# DRV8462.net
KiCad netlist of a schematic drawn in Altium Designer
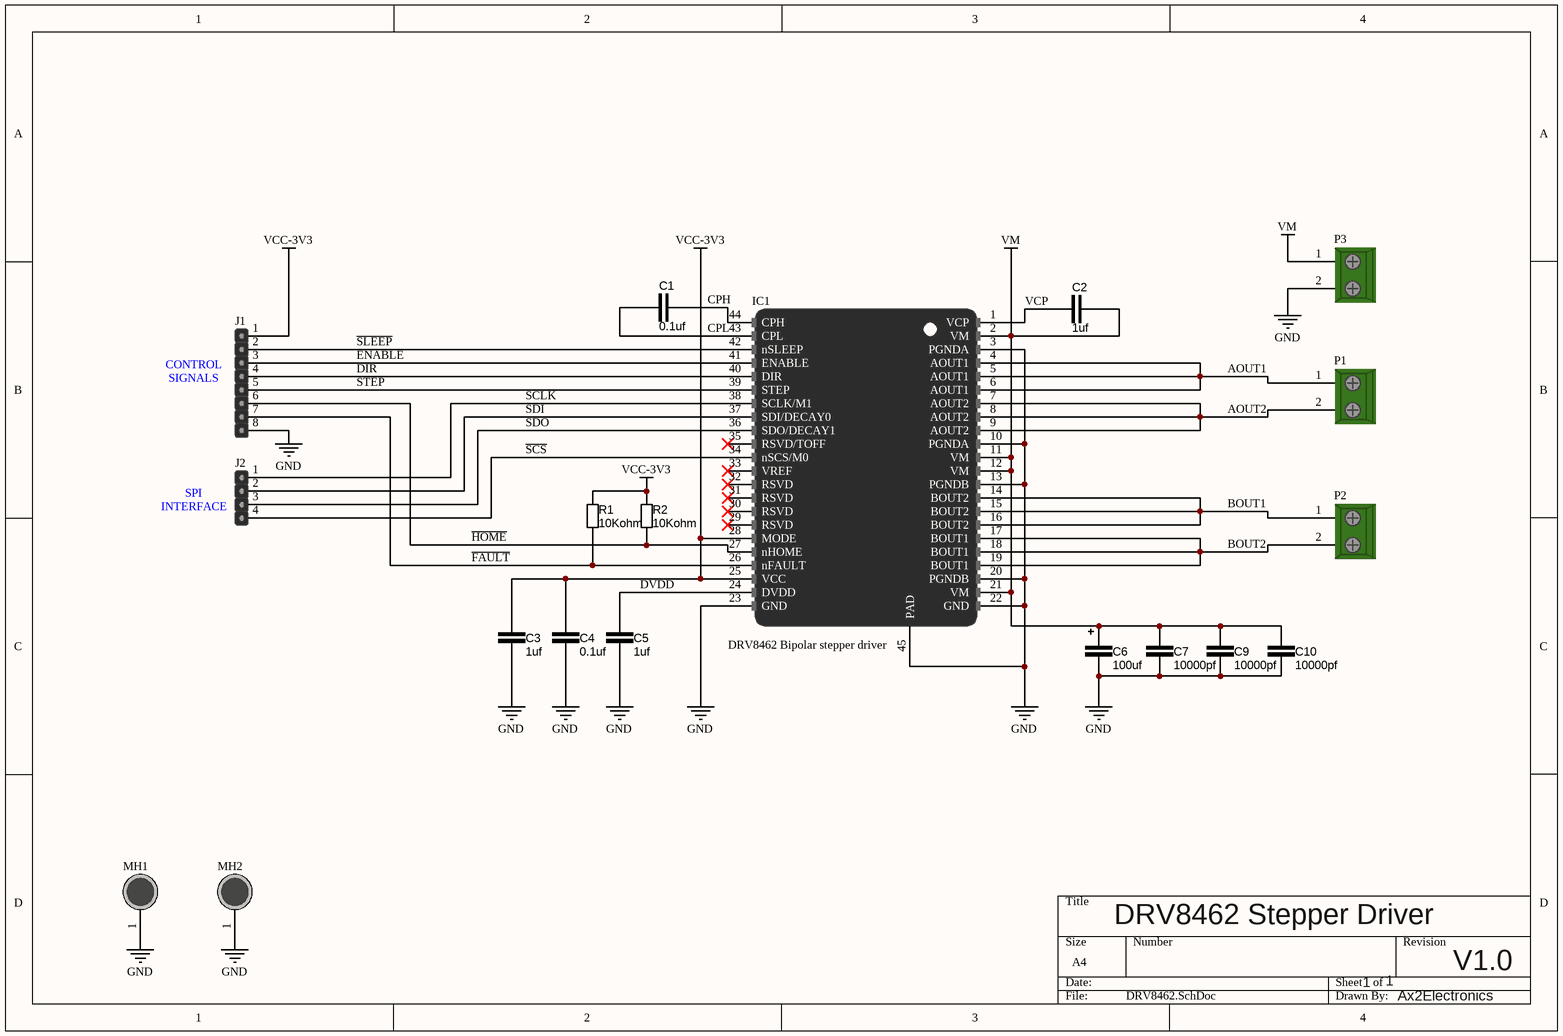
[diagram p0: DRV8462.SchDoc]

(export (version "E")
  (design (tool "Eeschema 10.0.6"))
  (components
    (comp (ref "C1")
      (value "0.1uf")
      (footprint "CAP_0603")
      (description "CAP CER 0.1uF 10V X7R 0603")
      (fields (field (name "DIGIKEY PART NUMBER") "732-7939-2-ND"))
      (libsource (lib "") (part "0000012_1"))
    )
    (comp (ref "C2")
      (value "1uf")
      (footprint "CAP_0603")
      (description "CAP CER 1uF 0603 16V X7R")
      (fields (field (name "DIGIKEY PART NUMBER") "1276-1019-2-ND"))
      (libsource (lib "CapacitorsIntegrated") (part "0000009"))
    )
    (comp (ref "C3")
      (value "1uf")
      (footprint "CAP_0603")
      (description "CAP CER 1uF 10V X7R 0603")
      (fields (field (name "DIGIKEY PART NUMBER") "1276-1946-2-ND"))
      (libsource (lib "CapacitorsIntegrated") (part "0000011"))
    )
    (comp (ref "C4")
      (value "0.1uf")
      (footprint "CAP_0603")
      (description "CAP CER 0.1uF 10V X7R 0603")
      (fields (field (name "DIGIKEY PART NUMBER") "732-7939-2-ND"))
      (libsource (lib "CapacitorsIntegrated") (part "0000012"))
    )
    (comp (ref "C5")
      (value "1uf")
      (footprint "CAP_0603")
      (description "CAP CER 1uF 0603 16V X7R")
      (fields (field (name "DIGIKEY PART NUMBER") "1276-1019-2-ND"))
      (libsource (lib "") (part "0000009_1"))
    )
    (comp (ref "C6")
      (value "100uf")
      (footprint "CAPAE7366X60M")
      (description "CAP ALUM POLY 100UF 20% 63V SMD")
      (fields (field (name "DIGIKEY PART NUMBER") "399-15648-2-ND"))
      (libsource (lib "CapacitorsIntegrated") (part "0000013"))
    )
    (comp (ref "C7")
      (value "10000pf")
      (footprint "CAP_0603")
      (description "CAP CER 10000PF 63V X7R 0603")
      (fields (field (name "DIGIKEY PART NUMBER") "1608-1294-2-ND"))
      (libsource (lib "CapacitorsIntegrated") (part "0000010"))
    )
    (comp (ref "C9")
      (value "10000pf")
      (footprint "CAP_0603")
      (description "CAP CER 10000PF 63V X7R 0603")
      (fields (field (name "DIGIKEY PART NUMBER") "1608-1294-2-ND"))
      (libsource (lib "CapacitorsIntegrated") (part "0000010"))
    )
    (comp (ref "C10")
      (value "10000pf")
      (footprint "CAP_0603")
      (description "CAP CER 10000PF 63V X7R 0603")
      (fields (field (name "DIGIKEY PART NUMBER") "1608-1294-2-ND"))
      (libsource (lib "CapacitorsIntegrated") (part "0000010"))
    )
    (comp (ref "IC1")
      (value "DRV8462 Bipolar stepper driver")
      (footprint "TSOP64P810X120_HS-45N")
      (description "65-V, 10-A, DUAL H-BRIDGE STEPPER DRIVER")
      (fields
        (field (name "DIGIKEY PART NUMBER") "296-DRV8462DDWRTR-ND")
        (field (name "MOUSER PART NUMBER") "595-DRV8462DDWR")
      )
      (libsource (lib "IntegratedCircuits") (part "DRV8462"))
    )
    (comp (ref "J1")
      (value "Header 8 PIN")
      (footprint "HEADER_8PIN")
      (libsource (lib "ElectroMechanical") (part "00000005"))
    )
    (comp (ref "J2")
      (value "Header 4 PIN")
      (footprint "HEADER_4PIN")
      (libsource (lib "ElectroMechanical") (part "00000004"))
    )
    (comp (ref "MH1")
      (value "Mounting Hole")
      (footprint "HOLE-3mm")
      (description "Mounting Hole 3mm")
      (libsource (lib "ElectroMechanical") (part "00000006"))
    )
    (comp (ref "MH2")
      (value "Mounting Hole")
      (footprint "HOLE-3mm")
      (description "Mounting Hole 3mm")
      (libsource (lib "ElectroMechanical") (part "00000006"))
    )
    (comp (ref "P1")
      (value "Terminal Block")
      (footprint "TERM_BLOCK 5mm 2PIN")
      (description "Terminal block 90 deg 5mm 2PIN")
      (fields (field (name "DIGIKEY PART NUMBER") "2057-EB20-02-C-ND"))
      (libsource (lib "ElectroMechanical") (part "00000001"))
    )
    (comp (ref "P2")
      (value "Terminal Block")
      (footprint "TERM_BLOCK 5mm 2PIN")
      (description "Terminal block 90 deg 5mm 2PIN")
      (fields (field (name "DIGIKEY PART NUMBER") "2057-EB20-02-C-ND"))
      (libsource (lib "ElectroMechanical") (part "00000001"))
    )
    (comp (ref "P3")
      (value "Terminal Block")
      (footprint "TERM_BLOCK 5mm 2PIN")
      (description "Terminal block 90 deg 5mm 2PIN")
      (fields (field (name "DIGIKEY PART NUMBER") "2057-EB20-02-C-ND"))
      (libsource (lib "ElectroMechanical") (part "00000001"))
    )
    (comp (ref "R1")
      (value "10Kohm")
      (footprint "RES_0603")
      (description "RES 10K OHM 1% 1/10W 0603")
      (libsource (lib "ResistorsIntegrated") (part "R000001"))
    )
    (comp (ref "R2")
      (value "10Kohm")
      (footprint "RES_0603")
      (description "RES 10K OHM 1% 1/10W 0603")
      (libsource (lib "ResistorsIntegrated") (part "R000001"))
    )
  )
  (nets
    (net (code "1") (name "/AOUT1") (class "Default")
      (node (ref "IC1") (pin "4") (pinfunction "AOUT1_4") (pintype "passive"))
      (node (ref "IC1") (pin "5") (pinfunction "AOUT1_5") (pintype "passive"))
      (node (ref "IC1") (pin "6") (pinfunction "AOUT1_6") (pintype "passive"))
      (node (ref "P1") (pin "1") (pinfunction "pin1_1") (pintype "passive"))
    )
    (net (code "2") (name "/AOUT2") (class "Default")
      (node (ref "IC1") (pin "7") (pinfunction "AOUT2_7") (pintype "passive"))
      (node (ref "IC1") (pin "8") (pinfunction "AOUT2_8") (pintype "passive"))
      (node (ref "IC1") (pin "9") (pinfunction "AOUT2_9") (pintype "passive"))
      (node (ref "P1") (pin "2") (pinfunction "pin2_2") (pintype "passive"))
    )
    (net (code "3") (name "/BOUT1") (class "Default")
      (node (ref "IC1") (pin "14") (pinfunction "BOUT2_14") (pintype "passive"))
      (node (ref "IC1") (pin "15") (pinfunction "BOUT2_15") (pintype "passive"))
      (node (ref "IC1") (pin "16") (pinfunction "BOUT2_16") (pintype "passive"))
      (node (ref "P2") (pin "1") (pinfunction "pin1_1") (pintype "passive"))
    )
    (net (code "4") (name "/BOUT2") (class "Default")
      (node (ref "IC1") (pin "17") (pinfunction "BOUT1_17") (pintype "passive"))
      (node (ref "IC1") (pin "18") (pinfunction "BOUT1_18") (pintype "passive"))
      (node (ref "IC1") (pin "19") (pinfunction "BOUT1_19") (pintype "passive"))
      (node (ref "P2") (pin "2") (pinfunction "pin2_2") (pintype "passive"))
    )
    (net (code "5") (name "/CPH") (class "Default")
      (node (ref "C1") (pin "2") (pinfunction "2_2") (pintype "passive"))
      (node (ref "IC1") (pin "44") (pinfunction "CPH_44") (pintype "passive"))
    )
    (net (code "6") (name "/CPL") (class "Default")
      (node (ref "C1") (pin "1") (pinfunction "1_1") (pintype "passive"))
      (node (ref "IC1") (pin "43") (pinfunction "CPL_43") (pintype "passive"))
    )
    (net (code "7") (name "/DIR") (class "Default")
      (node (ref "IC1") (pin "40") (pinfunction "DIR_40") (pintype "passive"))
      (node (ref "J1") (pin "4") (pinfunction "4_4") (pintype "passive"))
    )
    (net (code "8") (name "/DVDD") (class "Default")
      (node (ref "C5") (pin "2") (pinfunction "2_2") (pintype "passive"))
      (node (ref "IC1") (pin "24") (pinfunction "DVDD_24") (pintype "passive"))
    )
    (net (code "9") (name "/ENABLE") (class "Default")
      (node (ref "IC1") (pin "41") (pinfunction "ENABLE_41") (pintype "passive"))
      (node (ref "J1") (pin "3") (pinfunction "3_3") (pintype "passive"))
    )
    (net (code "10") (name "/SCLK") (class "Default")
      (node (ref "IC1") (pin "38") (pinfunction "SCLK/M1_38") (pintype "passive"))
      (node (ref "J2") (pin "1") (pinfunction "1_1") (pintype "passive"))
    )
    (net (code "11") (name "/SDI") (class "Default")
      (node (ref "IC1") (pin "37") (pinfunction "SDI/DECAY0_37") (pintype "passive"))
      (node (ref "J2") (pin "2") (pinfunction "2_2") (pintype "passive"))
    )
    (net (code "12") (name "/SDO") (class "Default")
      (node (ref "IC1") (pin "36") (pinfunction "SDO/DECAY1_36") (pintype "passive"))
      (node (ref "J2") (pin "3") (pinfunction "3_3") (pintype "passive"))
    )
    (net (code "13") (name "/STEP") (class "Default")
      (node (ref "IC1") (pin "39") (pinfunction "STEP_39") (pintype "passive"))
      (node (ref "J1") (pin "5") (pinfunction "5_5") (pintype "passive"))
    )
    (net (code "14") (name "/VCP") (class "Default")
      (node (ref "C2") (pin "1") (pinfunction "1_1") (pintype "passive"))
      (node (ref "IC1") (pin "1") (pinfunction "VCP_1") (pintype "passive"))
    )
    (net (code "15") (name "/~{FAULT}") (class "Default")
      (node (ref "IC1") (pin "26") (pinfunction "nFAULT_26") (pintype "passive"))
      (node (ref "J1") (pin "7") (pinfunction "7_7") (pintype "passive"))
      (node (ref "R1") (pin "1") (pinfunction "1_1") (pintype "passive"))
    )
    (net (code "16") (name "/~{HOME}") (class "Default")
      (node (ref "IC1") (pin "27") (pinfunction "nHOME_27") (pintype "passive"))
      (node (ref "J1") (pin "6") (pinfunction "6_6") (pintype "passive"))
      (node (ref "R2") (pin "1") (pinfunction "1_1") (pintype "passive"))
    )
    (net (code "17") (name "/~{SCS}") (class "Default")
      (node (ref "IC1") (pin "34") (pinfunction "nSCS/M0_34") (pintype "passive"))
      (node (ref "J2") (pin "4") (pinfunction "4_4") (pintype "passive"))
    )
    (net (code "18") (name "/~{SLEEP}") (class "Default")
      (node (ref "IC1") (pin "42") (pinfunction "nSLEEP_42") (pintype "passive"))
      (node (ref "J1") (pin "2") (pinfunction "2_2") (pintype "passive"))
    )
    (net (code "19") (name "GND") (class "Default")
      (node (ref "C10") (pin "1") (pinfunction "1_1") (pintype "passive"))
      (node (ref "C3") (pin "2") (pinfunction "2_2") (pintype "passive"))
      (node (ref "C4") (pin "1") (pinfunction "1_1") (pintype "passive"))
      (node (ref "C5") (pin "1") (pinfunction "1_1") (pintype "passive"))
      (node (ref "C6") (pin "1") (pinfunction "1_1") (pintype "passive"))
      (node (ref "C7") (pin "1") (pinfunction "1_1") (pintype "passive"))
      (node (ref "C9") (pin "1") (pinfunction "1_1") (pintype "passive"))
      (node (ref "IC1") (pin "10") (pinfunction "PGNDA_10") (pintype "passive"))
      (node (ref "IC1") (pin "13") (pinfunction "PGNDB_13") (pintype "passive"))
      (node (ref "IC1") (pin "20") (pinfunction "PGNDB_20") (pintype "passive"))
      (node (ref "IC1") (pin "22") (pinfunction "GND_22") (pintype "passive"))
      (node (ref "IC1") (pin "23") (pinfunction "GND_23") (pintype "passive"))
      (node (ref "IC1") (pin "3") (pinfunction "PGNDA_3") (pintype "passive"))
      (node (ref "IC1") (pin "45") (pinfunction "PAD_45") (pintype "passive"))
      (node (ref "J1") (pin "8") (pinfunction "8_8") (pintype "passive"))
      (node (ref "MH1") (pin "1") (pinfunction "1_1") (pintype "passive"))
      (node (ref "MH2") (pin "1") (pinfunction "1_1") (pintype "passive"))
      (node (ref "P3") (pin "2") (pinfunction "pin2_2") (pintype "passive"))
    )
    (net (code "20") (name "VCC-3V3") (class "Default")
      (node (ref "C3") (pin "1") (pinfunction "1_1") (pintype "passive"))
      (node (ref "C4") (pin "2") (pinfunction "2_2") (pintype "passive"))
      (node (ref "IC1") (pin "25") (pinfunction "VCC_25") (pintype "passive"))
      (node (ref "IC1") (pin "28") (pinfunction "MODE_28") (pintype "passive"))
      (node (ref "J1") (pin "1") (pinfunction "1_1") (pintype "passive"))
      (node (ref "R1") (pin "2") (pinfunction "2_2") (pintype "passive"))
      (node (ref "R2") (pin "2") (pinfunction "2_2") (pintype "passive"))
    )
    (net (code "21") (name "VM") (class "Default")
      (node (ref "C10") (pin "2") (pinfunction "2_2") (pintype "passive"))
      (node (ref "C2") (pin "2") (pinfunction "2_2") (pintype "passive"))
      (node (ref "C6") (pin "2") (pinfunction "2_2") (pintype "passive"))
      (node (ref "C7") (pin "2") (pinfunction "2_2") (pintype "passive"))
      (node (ref "C9") (pin "2") (pinfunction "2_2") (pintype "passive"))
      (node (ref "IC1") (pin "11") (pinfunction "VM_11") (pintype "passive"))
      (node (ref "IC1") (pin "12") (pinfunction "VM_12") (pintype "passive"))
      (node (ref "IC1") (pin "2") (pinfunction "VM_2") (pintype "passive"))
      (node (ref "IC1") (pin "21") (pinfunction "VM_21") (pintype "passive"))
      (node (ref "P3") (pin "1") (pinfunction "pin1_1") (pintype "passive"))
    )
    (net (code "22") (name "unconnected-(IC1-RSVD-Pad29)") (class "Default")
      (node (ref "IC1") (pin "29") (pinfunction "RSVD_29") (pintype "passive+no_connect"))
    )
    (net (code "23") (name "unconnected-(IC1-RSVD-Pad30)") (class "Default")
      (node (ref "IC1") (pin "30") (pinfunction "RSVD_30") (pintype "passive+no_connect"))
    )
    (net (code "24") (name "unconnected-(IC1-RSVD-Pad31)") (class "Default")
      (node (ref "IC1") (pin "31") (pinfunction "RSVD_31") (pintype "passive+no_connect"))
    )
    (net (code "25") (name "unconnected-(IC1-RSVD-Pad32)") (class "Default")
      (node (ref "IC1") (pin "32") (pinfunction "RSVD_32") (pintype "passive+no_connect"))
    )
    (net (code "26") (name "unconnected-(IC1-RSVD{slash}TOFF-Pad35)") (class "Default")
      (node (ref "IC1") (pin "35") (pinfunction "RSVD/TOFF_35") (pintype "passive+no_connect"))
    )
    (net (code "27") (name "unconnected-(IC1-VREF-Pad33)") (class "Default")
      (node (ref "IC1") (pin "33") (pinfunction "VREF_33") (pintype "passive+no_connect"))
    )
  )
)
